# DigitalComm.net
KiCad netlist of a schematic drawn in Altium Designer
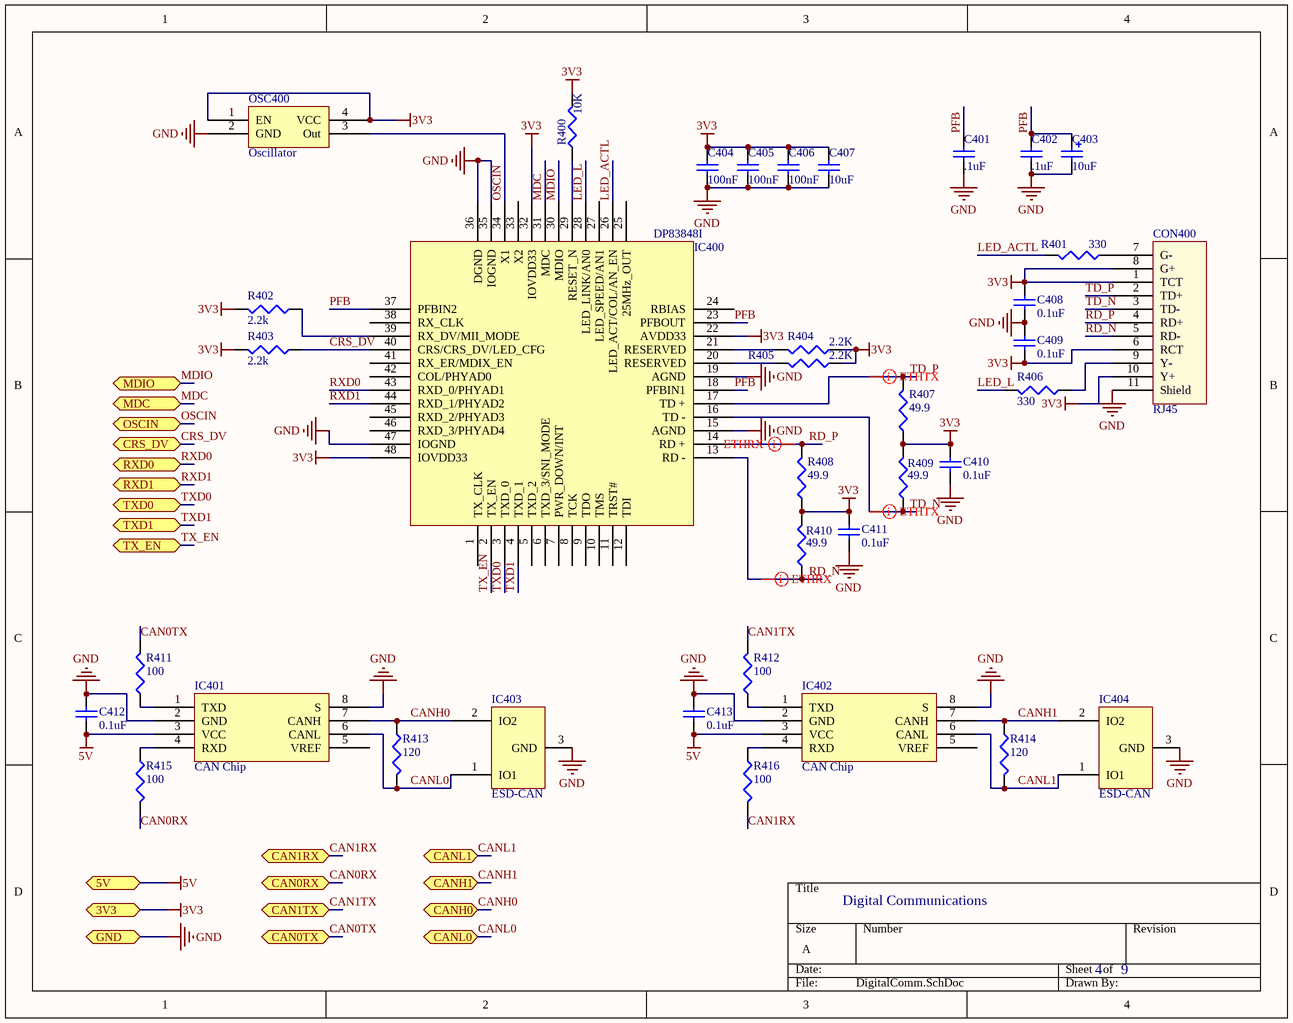
[diagram p0: DigitalComm.SchDoc]

(export (version "E")
  (design (tool "Eeschema 10.0.6"))
  (components
    (comp (ref "C401")
      (value ".1uF")
      (footprint "SMD0603")
      (description "Ceramic Chip Capacitor")
      (fields (field (name "Comment") "Capacitor Ceramic"))
      (libsource (lib "Components") (part "Capacitor Ceramic"))
    )
    (comp (ref "C402")
      (value ".1uF")
      (footprint "SMD0603")
      (description "Ceramic Chip Capacitor")
      (fields (field (name "Comment") "Capacitor Ceramic"))
      (libsource (lib "Components") (part "Capacitor Ceramic"))
    )
    (comp (ref "C403")
      (value "10uF")
      (footprint "SMD1206 Polarized")
      (description "Polarized Capacitor (Surface Mount)")
      (fields (field (name "Comment") "Cap"))
      (libsource (lib "Components") (part "Capacitor Polarized"))
    )
    (comp (ref "C404")
      (value "100nF")
      (footprint "SMD0603")
      (description "Ceramic Chip Capacitor")
      (fields (field (name "Comment") "Capacitor Ceramic"))
      (libsource (lib "Components") (part "Capacitor Ceramic"))
    )
    (comp (ref "C405")
      (value "100nF")
      (footprint "SMD0603")
      (description "Ceramic Chip Capacitor")
      (fields (field (name "Comment") "Capacitor Ceramic"))
      (libsource (lib "Components") (part "Capacitor Ceramic"))
    )
    (comp (ref "C406")
      (value "100nF")
      (footprint "SMD0603")
      (description "Ceramic Chip Capacitor")
      (fields (field (name "Comment") "Capacitor Ceramic"))
      (libsource (lib "Components") (part "Capacitor Ceramic"))
    )
    (comp (ref "C407")
      (value "10uF")
      (footprint "SMD0805")
      (description "Ceramic Chip Capacitor")
      (fields (field (name "Comment") "Capacitor Ceramic"))
      (libsource (lib "Components") (part "Capacitor Ceramic"))
    )
    (comp (ref "C408")
      (value "0.1uF")
      (footprint "SMD0603")
      (description "Ceramic Chip Capacitor")
      (fields (field (name "Comment") "Cap"))
      (libsource (lib "Components") (part "Capacitor Ceramic"))
    )
    (comp (ref "C409")
      (value "0.1uF")
      (footprint "SMD0603")
      (description "Ceramic Chip Capacitor")
      (fields (field (name "Comment") "Cap"))
      (libsource (lib "Components") (part "Capacitor Ceramic"))
    )
    (comp (ref "C410")
      (value "0.1uF")
      (footprint "SMD0603")
      (description "Ceramic Chip Capacitor")
      (fields (field (name "Comment") "Cap"))
      (libsource (lib "Components") (part "Capacitor Ceramic"))
    )
    (comp (ref "C411")
      (value "0.1uF")
      (footprint "SMD0603")
      (description "Ceramic Chip Capacitor")
      (fields (field (name "Comment") "Cap"))
      (libsource (lib "Components") (part "Capacitor Ceramic"))
    )
    (comp (ref "C412")
      (value "0.1uF")
      (footprint "SMD0603")
      (description "Ceramic Chip Capacitor")
      (fields (field (name "Comment") "Capacitor Ceramic"))
      (libsource (lib "Components") (part "Capacitor Ceramic"))
    )
    (comp (ref "C413")
      (value "0.1uF")
      (footprint "SMD0603")
      (description "Ceramic Chip Capacitor")
      (fields (field (name "Comment") "Capacitor Ceramic"))
      (libsource (lib "Components") (part "Capacitor Ceramic"))
    )
    (comp (ref "CON400")
      (value "RJ45")
      (footprint "RJ45")
      (description "RJ45 Ethernet Connector with built in magnetics")
      (libsource (lib "Components") (part "RJ45"))
    )
    (comp (ref "IC400")
      (value "DP83848I")
      (footprint "LQFP-48")
      (description "Ethernet PHY IC; compatitble with DP83848C")
      (libsource (lib "Components") (part "DP83848I"))
    )
    (comp (ref "IC401")
      (value "CAN Chip")
      (footprint "SOIC-8")
      (libsource (lib "Components") (part "SN65HVD1050"))
    )
    (comp (ref "IC402")
      (value "CAN Chip")
      (footprint "SOIC-8")
      (libsource (lib "Components") (part "SN65HVD1050"))
    )
    (comp (ref "IC403")
      (value "ESD-CAN")
      (footprint "SOT-23-3")
      (libsource (lib "Components") (part "ESDCAN24-2BLY"))
    )
    (comp (ref "IC404")
      (value "ESD-CAN")
      (footprint "SOT-23-3")
      (libsource (lib "Components") (part "ESDCAN24-2BLY"))
    )
    (comp (ref "OSC400")
      (value "Oscillator")
      (footprint "SM77H-OSC")
      (description "50Mhz Oscillator")
      (libsource (lib "Components") (part "SM7745HEV"))
    )
    (comp (ref "R400")
      (value "10K")
      (footprint "SMD0603")
      (description "Resistor")
      (fields (field (name "Comment") "Res"))
      (libsource (lib "Components") (part "Resistor"))
    )
    (comp (ref "R401")
      (value "330")
      (footprint "SMD0603")
      (description "Resistor")
      (fields (field (name "Comment") "Res"))
      (libsource (lib "Components") (part "Resistor"))
    )
    (comp (ref "R402")
      (value "2.2k")
      (footprint "SMD0603")
      (description "Resistor")
      (fields (field (name "Comment") "Res"))
      (libsource (lib "Components") (part "Resistor"))
    )
    (comp (ref "R403")
      (value "2.2k")
      (footprint "SMD0603")
      (description "Resistor")
      (fields (field (name "Comment") "Res"))
      (libsource (lib "Components") (part "Resistor"))
    )
    (comp (ref "R404")
      (value "2.2K")
      (footprint "SMD0603")
      (description "Resistor")
      (fields (field (name "Comment") "Res"))
      (libsource (lib "Components") (part "Resistor"))
    )
    (comp (ref "R405")
      (value "2.2K")
      (footprint "SMD0603")
      (description "Resistor")
      (fields (field (name "Comment") "Res"))
      (libsource (lib "Components") (part "Resistor"))
    )
    (comp (ref "R406")
      (value "330")
      (footprint "SMD0603")
      (description "Resistor")
      (fields (field (name "Comment") "Res"))
      (libsource (lib "Components") (part "Resistor"))
    )
    (comp (ref "R407")
      (value "49.9")
      (footprint "SMD0603")
      (description "Resistor")
      (fields (field (name "Comment") "Res"))
      (libsource (lib "Components") (part "Resistor"))
    )
    (comp (ref "R408")
      (value "49.9")
      (footprint "SMD0603")
      (description "Resistor")
      (fields (field (name "Comment") "Res"))
      (libsource (lib "Components") (part "Resistor"))
    )
    (comp (ref "R409")
      (value "49.9")
      (footprint "SMD0603")
      (description "Resistor")
      (fields (field (name "Comment") "Res"))
      (libsource (lib "Components") (part "Resistor"))
    )
    (comp (ref "R410")
      (value "49.9")
      (footprint "SMD0603")
      (description "Resistor")
      (fields (field (name "Comment") "Res"))
      (libsource (lib "Components") (part "Resistor"))
    )
    (comp (ref "R411")
      (value "100")
      (footprint "SMD0603")
      (description "Resistor")
      (fields (field (name "Comment") "Res"))
      (libsource (lib "Components") (part "Resistor"))
    )
    (comp (ref "R412")
      (value "100")
      (footprint "SMD0603")
      (description "Resistor")
      (fields (field (name "Comment") "Res"))
      (libsource (lib "Components") (part "Resistor"))
    )
    (comp (ref "R413")
      (value "120")
      (footprint "SMD0603")
      (description "Resistor")
      (fields (field (name "Comment") "Res"))
      (libsource (lib "Components") (part "Resistor"))
    )
    (comp (ref "R414")
      (value "120")
      (footprint "SMD0603")
      (description "Resistor")
      (fields (field (name "Comment") "Res"))
      (libsource (lib "Components") (part "Resistor"))
    )
    (comp (ref "R415")
      (value "100")
      (footprint "SMD0603")
      (description "Resistor")
      (fields (field (name "Comment") "Res"))
      (libsource (lib "Components") (part "Resistor"))
    )
    (comp (ref "R416")
      (value "100")
      (footprint "SMD0603")
      (description "Resistor")
      (fields (field (name "Comment") "Res"))
      (libsource (lib "Components") (part "Resistor"))
    )
  )
  (nets
    (net (code "1") (name "/CAN0RX") (class "Default")
      (node (ref "R415") (pin "2") (pinfunction "2_2") (pintype "passive"))
    )
    (net (code "2") (name "/CAN0TX") (class "Default")
      (node (ref "R411") (pin "2") (pinfunction "2_2") (pintype "passive"))
    )
    (net (code "3") (name "/CAN1RX") (class "Default")
      (node (ref "R416") (pin "2") (pinfunction "2_2") (pintype "passive"))
    )
    (net (code "4") (name "/CAN1TX") (class "Default")
      (node (ref "R412") (pin "2") (pinfunction "2_2") (pintype "passive"))
    )
    (net (code "5") (name "/CANH0") (class "Default")
      (node (ref "IC401") (pin "7") (pinfunction "CANH_7") (pintype "passive"))
      (node (ref "IC403") (pin "2") (pinfunction "IO2_2") (pintype "passive"))
      (node (ref "R413") (pin "1") (pinfunction "1_1") (pintype "passive"))
    )
    (net (code "6") (name "/CANH1") (class "Default")
      (node (ref "IC402") (pin "7") (pinfunction "CANH_7") (pintype "passive"))
      (node (ref "IC404") (pin "2") (pinfunction "IO2_2") (pintype "passive"))
      (node (ref "R414") (pin "1") (pinfunction "1_1") (pintype "passive"))
    )
    (net (code "7") (name "/CANL0") (class "Default")
      (node (ref "IC401") (pin "6") (pinfunction "CANL_6") (pintype "passive"))
      (node (ref "IC403") (pin "1") (pinfunction "IO1_1") (pintype "passive"))
      (node (ref "R413") (pin "2") (pinfunction "2_2") (pintype "passive"))
    )
    (net (code "8") (name "/CANL1") (class "Default")
      (node (ref "IC402") (pin "6") (pinfunction "CANL_6") (pintype "passive"))
      (node (ref "IC404") (pin "1") (pinfunction "IO1_1") (pintype "passive"))
      (node (ref "R414") (pin "2") (pinfunction "2_2") (pintype "passive"))
    )
    (net (code "9") (name "/CRS_DV") (class "Default")
      (node (ref "IC400") (pin "40") (pinfunction "CRS/CRS_DV/LED_CFG_40") (pintype "passive"))
      (node (ref "R403") (pin "1") (pinfunction "1_1") (pintype "passive"))
    )
    (net (code "10") (name "/LED_ACTL") (class "Default")
      (node (ref "IC400") (pin "26") (pinfunction "LED_ACT/COL/AN_EN_26") (pintype "passive"))
      (node (ref "R401") (pin "2") (pinfunction "2_2") (pintype "passive"))
    )
    (net (code "11") (name "/LED_L") (class "Default")
      (node (ref "IC400") (pin "28") (pinfunction "LED_LINK/AN0_28") (pintype "passive"))
      (node (ref "R406") (pin "2") (pinfunction "2_2") (pintype "passive"))
    )
    (net (code "12") (name "/MDC") (class "Default")
      (node (ref "IC400") (pin "31") (pinfunction "MDC_31") (pintype "passive"))
    )
    (net (code "13") (name "/MDIO") (class "Default")
      (node (ref "IC400") (pin "30") (pinfunction "MDIO_30") (pintype "passive"))
    )
    (net (code "14") (name "/OSCIN") (class "Default")
      (node (ref "IC400") (pin "34") (pinfunction "X1_34") (pintype "passive"))
      (node (ref "OSC400") (pin "3") (pinfunction "Out_3") (pintype "passive"))
    )
    (net (code "15") (name "/PFB") (class "Default")
      (node (ref "C401") (pin "2") (pinfunction "2_2") (pintype "passive"))
      (node (ref "C402") (pin "2") (pinfunction "2_2") (pintype "passive"))
      (node (ref "C403") (pin "1") (pinfunction "1_1") (pintype "passive"))
      (node (ref "IC400") (pin "18") (pinfunction "PFBIN1_18") (pintype "passive"))
      (node (ref "IC400") (pin "23") (pinfunction "PFBOUT_23") (pintype "passive"))
      (node (ref "IC400") (pin "37") (pinfunction "PFBIN2_37") (pintype "passive"))
    )
    (net (code "16") (name "/RD_N") (class "Default")
      (node (ref "CON400") (pin "5") (pinfunction "RD-_5") (pintype "passive"))
      (node (ref "IC400") (pin "13") (pinfunction "RD_-_13") (pintype "passive"))
      (node (ref "R410") (pin "1") (pinfunction "1_1") (pintype "passive"))
    )
    (net (code "17") (name "/RD_P") (class "Default")
      (node (ref "CON400") (pin "4") (pinfunction "RD+_4") (pintype "passive"))
      (node (ref "IC400") (pin "14") (pinfunction "RD_+_14") (pintype "passive"))
      (node (ref "R408") (pin "2") (pinfunction "2_2") (pintype "passive"))
    )
    (net (code "18") (name "/RXD0") (class "Default")
      (node (ref "IC400") (pin "43") (pinfunction "RXD_0/PHYAD1_43") (pintype "passive"))
    )
    (net (code "19") (name "/RXD1") (class "Default")
      (node (ref "IC400") (pin "44") (pinfunction "RXD_1/PHYAD2_44") (pintype "passive"))
    )
    (net (code "20") (name "/TD_N") (class "Default")
      (node (ref "CON400") (pin "3") (pinfunction "TD-_3") (pintype "passive"))
      (node (ref "IC400") (pin "16") (pinfunction "TD_-_16") (pintype "passive"))
      (node (ref "R409") (pin "1") (pinfunction "1_1") (pintype "passive"))
    )
    (net (code "21") (name "/TD_P") (class "Default")
      (node (ref "CON400") (pin "2") (pinfunction "TD+_2") (pintype "passive"))
      (node (ref "IC400") (pin "17") (pinfunction "TD_+_17") (pintype "passive"))
      (node (ref "R407") (pin "2") (pinfunction "2_2") (pintype "passive"))
    )
    (net (code "22") (name "/TXD0") (class "Default")
      (node (ref "IC400") (pin "3") (pinfunction "TXD_0_3") (pintype "passive"))
    )
    (net (code "23") (name "/TXD1") (class "Default")
      (node (ref "IC400") (pin "4") (pinfunction "TXD_1_4") (pintype "passive"))
    )
    (net (code "24") (name "/TX_EN") (class "Default")
      (node (ref "IC400") (pin "2") (pinfunction "TX_EN_2") (pintype "passive"))
    )
    (net (code "25") (name "3V3") (class "Default")
      (node (ref "C404") (pin "2") (pinfunction "2_2") (pintype "passive"))
      (node (ref "C405") (pin "2") (pinfunction "2_2") (pintype "passive"))
      (node (ref "C406") (pin "2") (pinfunction "2_2") (pintype "passive"))
      (node (ref "C407") (pin "2") (pinfunction "2_2") (pintype "passive"))
      (node (ref "C408") (pin "2") (pinfunction "2_2") (pintype "passive"))
      (node (ref "C409") (pin "1") (pinfunction "1_1") (pintype "passive"))
      (node (ref "C410") (pin "2") (pinfunction "2_2") (pintype "passive"))
      (node (ref "C411") (pin "2") (pinfunction "2_2") (pintype "passive"))
      (node (ref "CON400") (pin "1") (pinfunction "TCT_1") (pintype "passive"))
      (node (ref "CON400") (pin "10") (pinfunction "Y+_10") (pintype "passive"))
      (node (ref "CON400") (pin "6") (pinfunction "RCT_6") (pintype "passive"))
      (node (ref "CON400") (pin "8") (pinfunction "G+_8") (pintype "passive"))
      (node (ref "IC400") (pin "22") (pinfunction "AVDD33_22") (pintype "passive"))
      (node (ref "IC400") (pin "32") (pinfunction "IOVDD33_32") (pintype "passive"))
      (node (ref "IC400") (pin "48") (pinfunction "IOVDD33_48") (pintype "passive"))
      (node (ref "OSC400") (pin "1") (pinfunction "EN_1") (pintype "passive"))
      (node (ref "OSC400") (pin "4") (pinfunction "VCC_4") (pintype "passive"))
      (node (ref "R400") (pin "2") (pinfunction "2_2") (pintype "passive"))
      (node (ref "R402") (pin "2") (pinfunction "2_2") (pintype "passive"))
      (node (ref "R403") (pin "2") (pinfunction "2_2") (pintype "passive"))
      (node (ref "R404") (pin "1") (pinfunction "1_1") (pintype "passive"))
      (node (ref "R405") (pin "1") (pinfunction "1_1") (pintype "passive"))
      (node (ref "R407") (pin "1") (pinfunction "1_1") (pintype "passive"))
      (node (ref "R408") (pin "1") (pinfunction "1_1") (pintype "passive"))
      (node (ref "R409") (pin "2") (pinfunction "2_2") (pintype "passive"))
      (node (ref "R410") (pin "2") (pinfunction "2_2") (pintype "passive"))
    )
    (net (code "26") (name "5V") (class "Default")
      (node (ref "C412") (pin "1") (pinfunction "1_1") (pintype "passive"))
      (node (ref "C413") (pin "1") (pinfunction "1_1") (pintype "passive"))
      (node (ref "IC401") (pin "3") (pinfunction "VCC_3") (pintype "passive"))
      (node (ref "IC402") (pin "3") (pinfunction "VCC_3") (pintype "passive"))
    )
    (net (code "27") (name "GND") (class "Default")
      (node (ref "C401") (pin "1") (pinfunction "1_1") (pintype "passive"))
      (node (ref "C402") (pin "1") (pinfunction "1_1") (pintype "passive"))
      (node (ref "C403") (pin "2") (pinfunction "2_2") (pintype "passive"))
      (node (ref "C404") (pin "1") (pinfunction "1_1") (pintype "passive"))
      (node (ref "C405") (pin "1") (pinfunction "1_1") (pintype "passive"))
      (node (ref "C406") (pin "1") (pinfunction "1_1") (pintype "passive"))
      (node (ref "C407") (pin "1") (pinfunction "1_1") (pintype "passive"))
      (node (ref "C408") (pin "1") (pinfunction "1_1") (pintype "passive"))
      (node (ref "C409") (pin "2") (pinfunction "2_2") (pintype "passive"))
      (node (ref "C410") (pin "1") (pinfunction "1_1") (pintype "passive"))
      (node (ref "C411") (pin "1") (pinfunction "1_1") (pintype "passive"))
      (node (ref "C412") (pin "2") (pinfunction "2_2") (pintype "passive"))
      (node (ref "C413") (pin "2") (pinfunction "2_2") (pintype "passive"))
      (node (ref "CON400") (pin "11") (pinfunction "Shield_11") (pintype "passive"))
      (node (ref "IC400") (pin "15") (pinfunction "AGND_15") (pintype "passive"))
      (node (ref "IC400") (pin "19") (pinfunction "AGND_19") (pintype "passive"))
      (node (ref "IC400") (pin "35") (pinfunction "IOGND_35") (pintype "passive"))
      (node (ref "IC400") (pin "36") (pinfunction "DGND_36") (pintype "passive"))
      (node (ref "IC400") (pin "47") (pinfunction "IOGND_47") (pintype "passive"))
      (node (ref "IC401") (pin "2") (pinfunction "GND_2") (pintype "passive"))
      (node (ref "IC401") (pin "8") (pinfunction "S_8") (pintype "passive"))
      (node (ref "IC402") (pin "2") (pinfunction "GND_2") (pintype "passive"))
      (node (ref "IC402") (pin "8") (pinfunction "S_8") (pintype "passive"))
      (node (ref "IC403") (pin "3") (pinfunction "GND_3") (pintype "passive"))
      (node (ref "IC404") (pin "3") (pinfunction "GND_3") (pintype "passive"))
      (node (ref "OSC400") (pin "2") (pinfunction "GND_2") (pintype "passive"))
    )
    (net (code "28") (name "Net-(CON400-G-)") (class "Default")
      (node (ref "CON400") (pin "7") (pinfunction "G-_7") (pintype "passive"))
      (node (ref "R401") (pin "1") (pinfunction "1_1") (pintype "passive"))
    )
    (net (code "29") (name "Net-(CON400-Y-)") (class "Default")
      (node (ref "CON400") (pin "9") (pinfunction "Y-_9") (pintype "passive"))
      (node (ref "R406") (pin "1") (pinfunction "1_1") (pintype "passive"))
    )
    (net (code "30") (name "Net-(IC400-RESERVED-Pad20)") (class "Default")
      (node (ref "IC400") (pin "20") (pinfunction "RESERVED_20") (pintype "passive"))
      (node (ref "R405") (pin "2") (pinfunction "2_2") (pintype "passive"))
    )
    (net (code "31") (name "Net-(IC400-RESERVED-Pad21)") (class "Default")
      (node (ref "IC400") (pin "21") (pinfunction "RESERVED_21") (pintype "passive"))
      (node (ref "R404") (pin "2") (pinfunction "2_2") (pintype "passive"))
    )
    (net (code "32") (name "Net-(IC400-RESET_N)") (class "Default")
      (node (ref "IC400") (pin "29") (pinfunction "RESET_N_29") (pintype "passive"))
      (node (ref "R400") (pin "1") (pinfunction "1_1") (pintype "passive"))
    )
    (net (code "33") (name "Net-(IC400-RX_DV{slash}MII_MODE)") (class "Default")
      (node (ref "IC400") (pin "39") (pinfunction "RX_DV/MII_MODE_39") (pintype "passive"))
      (node (ref "R402") (pin "1") (pinfunction "1_1") (pintype "passive"))
    )
    (net (code "34") (name "Net-(IC401-RXD)") (class "Default")
      (node (ref "IC401") (pin "4") (pinfunction "RXD_4") (pintype "passive"))
      (node (ref "R415") (pin "1") (pinfunction "1_1") (pintype "passive"))
    )
    (net (code "35") (name "Net-(IC401-TXD)") (class "Default")
      (node (ref "IC401") (pin "1") (pinfunction "TXD_1") (pintype "passive"))
      (node (ref "R411") (pin "1") (pinfunction "1_1") (pintype "passive"))
    )
    (net (code "36") (name "Net-(IC402-RXD)") (class "Default")
      (node (ref "IC402") (pin "4") (pinfunction "RXD_4") (pintype "passive"))
      (node (ref "R416") (pin "1") (pinfunction "1_1") (pintype "passive"))
    )
    (net (code "37") (name "Net-(IC402-TXD)") (class "Default")
      (node (ref "IC402") (pin "1") (pinfunction "TXD_1") (pintype "passive"))
      (node (ref "R412") (pin "1") (pinfunction "1_1") (pintype "passive"))
    )
    (net (code "38") (name "unconnected-(IC400-25MHz_OUT-Pad25)") (class "Default")
      (node (ref "IC400") (pin "25") (pinfunction "25MHz_OUT_25") (pintype "passive"))
    )
    (net (code "39") (name "unconnected-(IC400-COL{slash}PHYAD0-Pad42)") (class "Default")
      (node (ref "IC400") (pin "42") (pinfunction "COL/PHYAD0_42") (pintype "passive"))
    )
    (net (code "40") (name "unconnected-(IC400-LED_SPEED{slash}AN1-Pad27)") (class "Default")
      (node (ref "IC400") (pin "27") (pinfunction "LED_SPEED/AN1_27") (pintype "passive"))
    )
    (net (code "41") (name "unconnected-(IC400-PWR_DOWN{slash}INT-Pad7)") (class "Default")
      (node (ref "IC400") (pin "7") (pinfunction "PWR_DOWN/INT_7") (pintype "passive"))
    )
    (net (code "42") (name "unconnected-(IC400-RBIAS-Pad24)") (class "Default")
      (node (ref "IC400") (pin "24") (pinfunction "RBIAS_24") (pintype "passive"))
    )
    (net (code "43") (name "unconnected-(IC400-RXD_2{slash}PHYAD3-Pad45)") (class "Default")
      (node (ref "IC400") (pin "45") (pinfunction "RXD_2/PHYAD3_45") (pintype "passive"))
    )
    (net (code "44") (name "unconnected-(IC400-RXD_3{slash}PHYAD4-Pad46)") (class "Default")
      (node (ref "IC400") (pin "46") (pinfunction "RXD_3/PHYAD4_46") (pintype "passive"))
    )
    (net (code "45") (name "unconnected-(IC400-RX_CLK-Pad38)") (class "Default")
      (node (ref "IC400") (pin "38") (pinfunction "RX_CLK_38") (pintype "passive"))
    )
    (net (code "46") (name "unconnected-(IC400-RX_ER{slash}MDIX_EN-Pad41)") (class "Default")
      (node (ref "IC400") (pin "41") (pinfunction "RX_ER/MDIX_EN_41") (pintype "passive"))
    )
    (net (code "47") (name "unconnected-(IC400-TCK-Pad8)") (class "Default")
      (node (ref "IC400") (pin "8") (pinfunction "TCK_8") (pintype "passive"))
    )
    (net (code "48") (name "unconnected-(IC400-TDI-Pad12)") (class "Default")
      (node (ref "IC400") (pin "12") (pinfunction "TDI_12") (pintype "passive"))
    )
    (net (code "49") (name "unconnected-(IC400-TDO-Pad9)") (class "Default")
      (node (ref "IC400") (pin "9") (pinfunction "TDO_9") (pintype "passive"))
    )
    (net (code "50") (name "unconnected-(IC400-TMS-Pad10)") (class "Default")
      (node (ref "IC400") (pin "10") (pinfunction "TMS_10") (pintype "passive"))
    )
    (net (code "51") (name "unconnected-(IC400-TRST#-Pad11)") (class "Default")
      (node (ref "IC400") (pin "11") (pinfunction "TRST#_11") (pintype "passive"))
    )
    (net (code "52") (name "unconnected-(IC400-TXD_2-Pad5)") (class "Default")
      (node (ref "IC400") (pin "5") (pinfunction "TXD_2_5") (pintype "passive"))
    )
    (net (code "53") (name "unconnected-(IC400-TXD_3{slash}SNI_MODE-Pad6)") (class "Default")
      (node (ref "IC400") (pin "6") (pinfunction "TXD_3/SNI_MODE_6") (pintype "passive"))
    )
    (net (code "54") (name "unconnected-(IC400-TX_CLK-Pad1)") (class "Default")
      (node (ref "IC400") (pin "1") (pinfunction "TX_CLK_1") (pintype "passive"))
    )
    (net (code "55") (name "unconnected-(IC400-X2-Pad33)") (class "Default")
      (node (ref "IC400") (pin "33") (pinfunction "X2_33") (pintype "passive"))
    )
    (net (code "56") (name "unconnected-(IC401-VREF-Pad5)") (class "Default")
      (node (ref "IC401") (pin "5") (pinfunction "VREF_5") (pintype "passive"))
    )
    (net (code "57") (name "unconnected-(IC402-VREF-Pad5)") (class "Default")
      (node (ref "IC402") (pin "5") (pinfunction "VREF_5") (pintype "passive"))
    )
  )
)
